# 5v_ac_to_dc.net
KiCad netlist of a schematic drawn in EAGLE
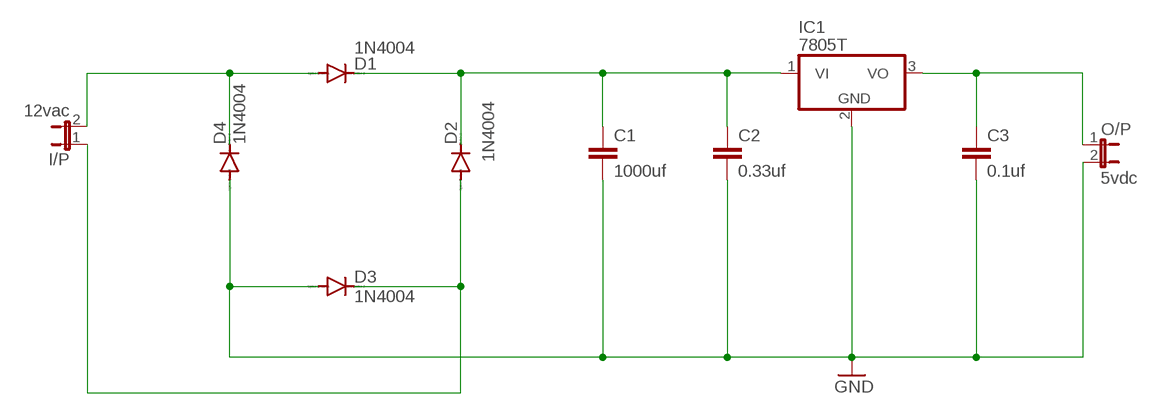
[diagram p0: schematic, sheet 1]

(export (version "E")
  (design (tool "Eeschema 10.0.6"))
  (components
    (comp (ref "C1")
      (value "1000uf")
      (footprint "eagle-import:C2.5-3")
      (libsource (lib "eagle-import") (part "C2,5-3"))
    )
    (comp (ref "C2")
      (value "0.33uf")
      (footprint "eagle-import:C2.5-3")
      (libsource (lib "eagle-import") (part "C2,5-3"))
    )
    (comp (ref "C3")
      (value "0.1uf")
      (footprint "eagle-import:C2.5-3")
      (libsource (lib "eagle-import") (part "C2,5-3"))
    )
    (comp (ref "D1")
      (value "1N4004")
      (footprint "eagle-import:DO41-10")
      (libsource (lib "eagle-import") (part "1N4004"))
    )
    (comp (ref "D2")
      (value "1N4004")
      (footprint "eagle-import:DO41-10")
      (libsource (lib "eagle-import") (part "1N4004"))
    )
    (comp (ref "D3")
      (value "1N4004")
      (footprint "eagle-import:DO41-10")
      (libsource (lib "eagle-import") (part "1N4004"))
    )
    (comp (ref "D4")
      (value "1N4004")
      (footprint "eagle-import:DO41-10")
      (libsource (lib "eagle-import") (part "1N4004"))
    )
    (comp (ref "I/P")
      (value "12vac")
      (footprint "eagle-import:JP1")
      (libsource (lib "eagle-import") (part "JP1E"))
    )
    (comp (ref "IC1")
      (value "7805T")
      (footprint "eagle-import:TO220H")
      (libsource (lib "eagle-import") (part "78T05"))
    )
    (comp (ref "O/P")
      (value "5vdc")
      (footprint "eagle-import:JP1")
      (libsource (lib "eagle-import") (part "JP1E"))
    )
  )
  (nets
    (net (code "1") (name "GND") (class "Default")
      (node (ref "C1") (pin "2") (pinfunction "2_2") (pintype "passive"))
      (node (ref "C2") (pin "2") (pinfunction "2_2") (pintype "passive"))
      (node (ref "C3") (pin "2") (pinfunction "2_2") (pintype "passive"))
      (node (ref "D3") (pin "A") (pinfunction "A_A") (pintype "passive"))
      (node (ref "D4") (pin "A") (pinfunction "A_A") (pintype "passive"))
      (node (ref "IC1") (pin "2") (pinfunction "GND_2") (pintype "passive"))
      (node (ref "O/P") (pin "2") (pinfunction "2_2") (pintype "passive"))
    )
    (net (code "2") (name "Net-(D1-PadA)") (class "Default")
      (node (ref "D1") (pin "A") (pinfunction "A_A") (pintype "passive"))
      (node (ref "D4") (pin "C") (pinfunction "C_C") (pintype "passive"))
      (node (ref "I/P") (pin "2") (pinfunction "2_2") (pintype "passive"))
    )
    (net (code "3") (name "Net-(D2-PadA)") (class "Default")
      (node (ref "D2") (pin "A") (pinfunction "A_A") (pintype "passive"))
      (node (ref "D3") (pin "C") (pinfunction "C_C") (pintype "passive"))
      (node (ref "I/P") (pin "1") (pinfunction "1_1") (pintype "passive"))
    )
    (net (code "4") (name "Net-(IC1-VI)") (class "Default")
      (node (ref "C1") (pin "1") (pinfunction "1_1") (pintype "passive"))
      (node (ref "C2") (pin "1") (pinfunction "1_1") (pintype "passive"))
      (node (ref "D1") (pin "C") (pinfunction "C_C") (pintype "passive"))
      (node (ref "D2") (pin "C") (pinfunction "C_C") (pintype "passive"))
      (node (ref "IC1") (pin "1") (pinfunction "VI_1") (pintype "input"))
    )
    (net (code "5") (name "Net-(IC1-VO)") (class "Default")
      (node (ref "C3") (pin "1") (pinfunction "1_1") (pintype "passive"))
      (node (ref "IC1") (pin "3") (pinfunction "VO_3") (pintype "passive"))
      (node (ref "O/P") (pin "1") (pinfunction "1_1") (pintype "passive"))
    )
  )
)
